# pic-lcd-std.net
KiCad netlist of a schematic drawn in EAGLE
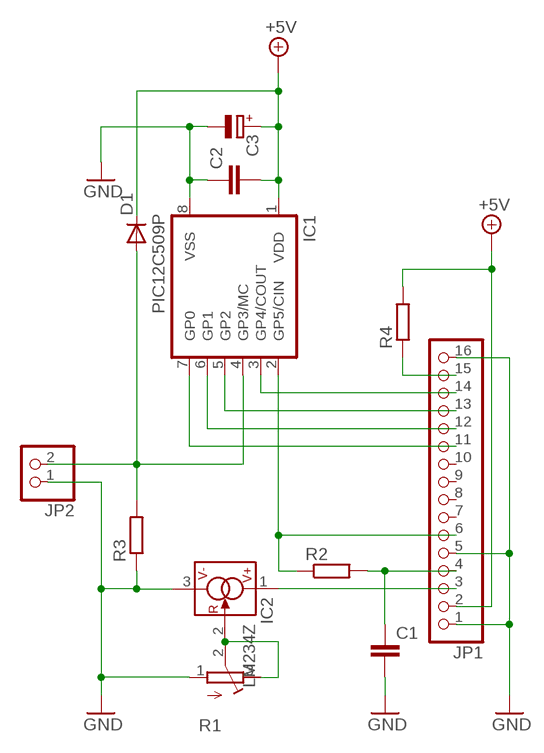
[diagram p0: schematic, sheet 1]

(export (version "E")
  (design (tool "Eeschema 10.0.6"))
  (components
    (comp (ref "C1")
      (value "C-EU025-025X050")
      (footprint "eagle-import:C025-025X050")
      (libsource (lib "eagle-import") (part "C-EU025-025X050"))
    )
    (comp (ref "C2")
      (value "C-EU025-025X050")
      (footprint "eagle-import:C025-025X050")
      (libsource (lib "eagle-import") (part "C-EU025-025X050"))
    )
    (comp (ref "C3")
      (value "CPOL-EUTT2D5L")
      (footprint "eagle-import:TT2D5L")
      (libsource (lib "eagle-import") (part "CPOL-EUTT2D5L"))
    )
    (comp (ref "D1")
      (value "DIODE-DO34-7")
      (footprint "eagle-import:DO34-7")
      (libsource (lib "eagle-import") (part "DIODE-DO34-7"))
    )
    (comp (ref "IC1")
      (value "PIC12C509P")
      (footprint "eagle-import:DIL8")
      (fields (field (name "MF") "MICROCHIP") (field (name "MPN") "PIC12C509-04/P"))
      (libsource (lib "eagle-import") (part "PIC12C?P509"))
    )
    (comp (ref "IC2")
      (value "LM234Z")
      (footprint "eagle-import:TO92")
      (libsource (lib "eagle-import") (part "LM34Z2"))
    )
    (comp (ref "JP1")
      (value "PINHD-1X16")
      (footprint "eagle-import:1X16")
      (libsource (lib "eagle-import") (part "PINHD-1X16"))
    )
    (comp (ref "JP2")
      (value "PINHD-1X2/90")
      (footprint "eagle-import:1X02_90")
      (libsource (lib "eagle-import") (part "PINHD-1X2/90"))
    )
    (comp (ref "R1")
      (value "R-TRIMM3296P")
      (footprint "eagle-import:RTRIM3296P")
      (libsource (lib "eagle-import") (part "R-TRIMM3296P"))
    )
    (comp (ref "R2")
      (value "R-EU_0204/7")
      (footprint "eagle-import:0204_7")
      (libsource (lib "eagle-import") (part "R-EU_0204/7"))
    )
    (comp (ref "R3")
      (value "R-EU_0204/7")
      (footprint "eagle-import:0204_7")
      (libsource (lib "eagle-import") (part "R-EU_0204/7"))
    )
    (comp (ref "R4")
      (value "R-EU_0204/7")
      (footprint "eagle-import:0204_7")
      (libsource (lib "eagle-import") (part "R-EU_0204/7"))
    )
  )
  (nets
    (net (code "1") (name "+5V") (class "Default")
      (node (ref "C2") (pin "2") (pinfunction "2_2") (pintype "passive"))
      (node (ref "C3") (pin "+") (pinfunction "+_+") (pintype "passive"))
      (node (ref "D1") (pin "C") (pinfunction "C_C") (pintype "passive"))
      (node (ref "IC1") (pin "1") (pinfunction "VDD_1") (pintype "power_in"))
      (node (ref "JP1") (pin "2") (pinfunction "2_2") (pintype "passive"))
      (node (ref "R4") (pin "2") (pinfunction "2_2") (pintype "passive"))
    )
    (net (code "2") (name "GND") (class "Default")
      (node (ref "C1") (pin "2") (pinfunction "2_2") (pintype "passive"))
      (node (ref "C2") (pin "1") (pinfunction "1_1") (pintype "passive"))
      (node (ref "C3") (pin "-") (pinfunction "-_-") (pintype "passive"))
      (node (ref "IC1") (pin "8") (pinfunction "VSS_8") (pintype "power_in"))
      (node (ref "IC2") (pin "3") (pinfunction "V-_3") (pintype "passive"))
      (node (ref "JP1") (pin "1") (pinfunction "1_1") (pintype "passive"))
      (node (ref "JP1") (pin "16") (pinfunction "16_16") (pintype "passive"))
      (node (ref "JP1") (pin "5") (pinfunction "5_5") (pintype "passive"))
      (node (ref "JP2") (pin "1") (pinfunction "1_1") (pintype "passive"))
      (node (ref "R1") (pin "1") (pinfunction "A_1") (pintype "passive"))
      (node (ref "R3") (pin "1") (pinfunction "1_1") (pintype "passive"))
    )
    (net (code "3") (name "Net-(C1-Pad1)") (class "Default")
      (node (ref "C1") (pin "1") (pinfunction "1_1") (pintype "passive"))
      (node (ref "JP1") (pin "4") (pinfunction "4_4") (pintype "passive"))
      (node (ref "R2") (pin "2") (pinfunction "2_2") (pintype "passive"))
    )
    (net (code "4") (name "Net-(IC1-GP0)") (class "Default")
      (node (ref "IC1") (pin "7") (pinfunction "GP0_7") (pintype "bidirectional"))
      (node (ref "JP1") (pin "11") (pinfunction "11_11") (pintype "passive"))
    )
    (net (code "5") (name "Net-(IC1-GP1)") (class "Default")
      (node (ref "IC1") (pin "6") (pinfunction "GP1_6") (pintype "bidirectional"))
      (node (ref "JP1") (pin "12") (pinfunction "12_12") (pintype "passive"))
    )
    (net (code "6") (name "Net-(IC1-GP2)") (class "Default")
      (node (ref "IC1") (pin "5") (pinfunction "GP2_5") (pintype "bidirectional"))
      (node (ref "JP1") (pin "13") (pinfunction "13_13") (pintype "passive"))
    )
    (net (code "7") (name "Net-(IC1-GP3{slash}MC)") (class "Default")
      (node (ref "D1") (pin "A") (pinfunction "A_A") (pintype "passive"))
      (node (ref "IC1") (pin "4") (pinfunction "GP3/MC_4") (pintype "input"))
      (node (ref "JP2") (pin "2") (pinfunction "2_2") (pintype "passive"))
      (node (ref "R3") (pin "2") (pinfunction "2_2") (pintype "passive"))
    )
    (net (code "8") (name "Net-(IC1-GP4{slash}COUT)") (class "Default")
      (node (ref "IC1") (pin "3") (pinfunction "GP4/COUT_3") (pintype "bidirectional"))
      (node (ref "JP1") (pin "14") (pinfunction "14_14") (pintype "passive"))
    )
    (net (code "9") (name "Net-(IC1-GP5{slash}CIN)") (class "Default")
      (node (ref "IC1") (pin "2") (pinfunction "GP5/CIN_2") (pintype "bidirectional"))
      (node (ref "JP1") (pin "6") (pinfunction "6_6") (pintype "passive"))
      (node (ref "R2") (pin "1") (pinfunction "1_1") (pintype "passive"))
    )
    (net (code "10") (name "Net-(IC2-R)") (class "Default")
      (node (ref "IC2") (pin "2") (pinfunction "R_2") (pintype "passive"))
      (node (ref "R1") (pin "2") (pinfunction "S_2") (pintype "passive"))
      (node (ref "R1") (pin "3") (pinfunction "E_3") (pintype "passive"))
    )
    (net (code "11") (name "Net-(IC2-V+)") (class "Default")
      (node (ref "IC2") (pin "1") (pinfunction "V+_1") (pintype "passive"))
      (node (ref "JP1") (pin "3") (pinfunction "3_3") (pintype "passive"))
    )
    (net (code "12") (name "Net-(JP1-Pad15)") (class "Default")
      (node (ref "JP1") (pin "15") (pinfunction "15_15") (pintype "passive"))
      (node (ref "R4") (pin "1") (pinfunction "1_1") (pintype "passive"))
    )
    (net (code "13") (name "unconnected-(JP1-Pad7)") (class "Default")
      (node (ref "JP1") (pin "7") (pinfunction "7_7") (pintype "passive"))
    )
    (net (code "14") (name "unconnected-(JP1-Pad8)") (class "Default")
      (node (ref "JP1") (pin "8") (pinfunction "8_8") (pintype "passive"))
    )
    (net (code "15") (name "unconnected-(JP1-Pad9)") (class "Default")
      (node (ref "JP1") (pin "9") (pinfunction "9_9") (pintype "passive"))
    )
    (net (code "16") (name "unconnected-(JP1-Pad10)") (class "Default")
      (node (ref "JP1") (pin "10") (pinfunction "10_10") (pintype "passive"))
    )
  )
)
